# PSU-triple-voltage-eagle-6-branded.net
KiCad netlist of a schematic drawn in EAGLE
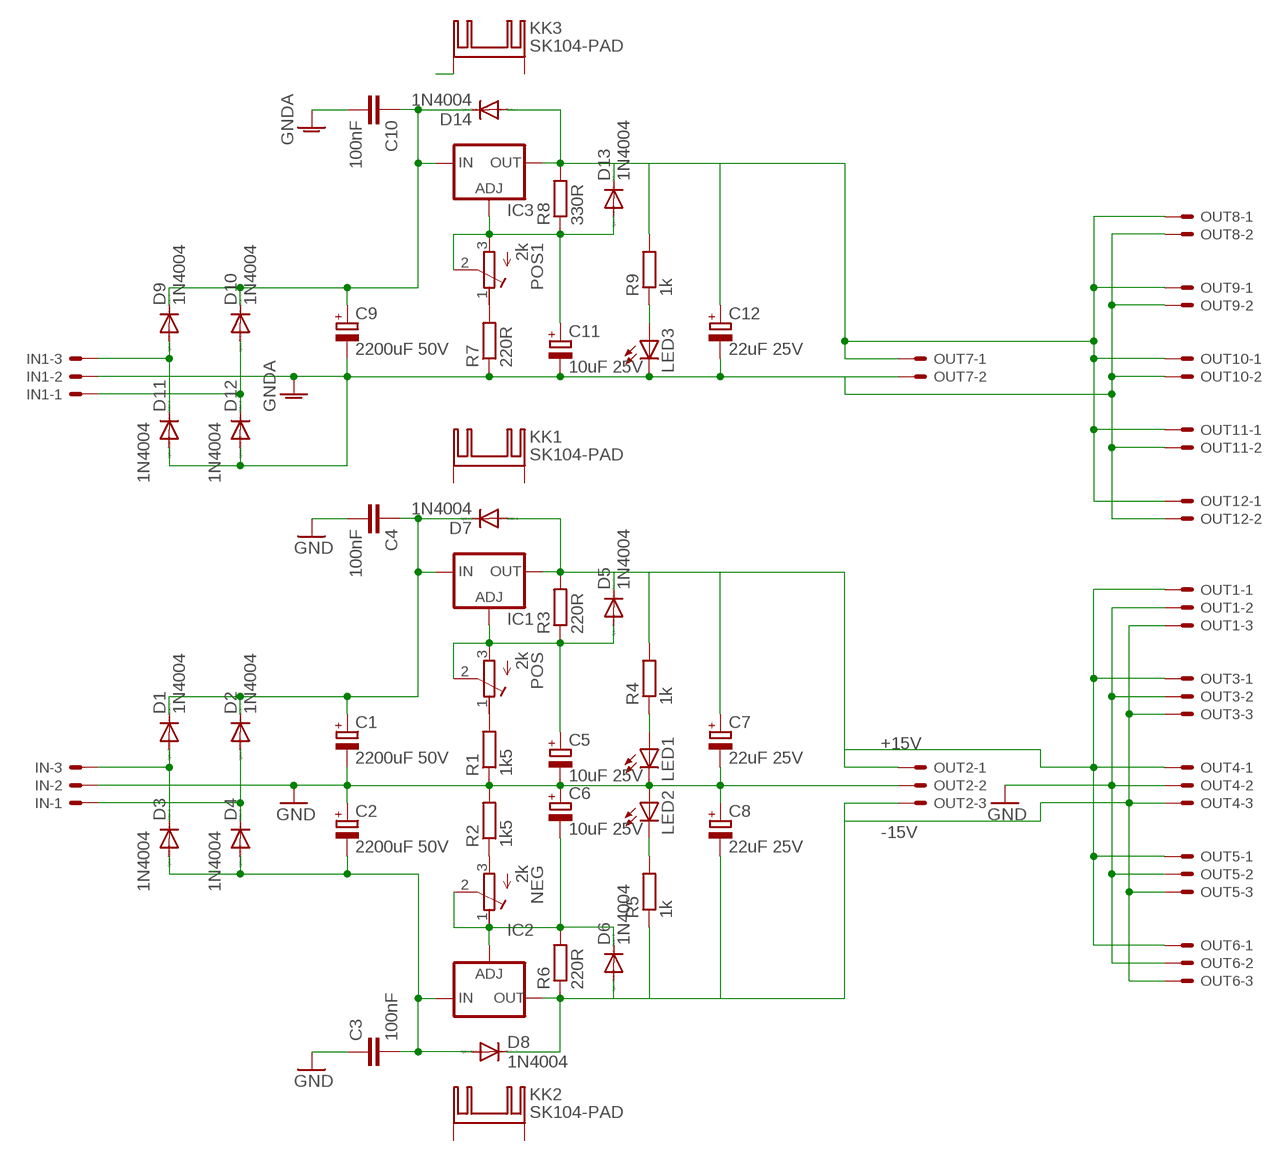
[diagram p0: schematic, sheet 1]

(export (version "E")
  (design (tool "Eeschema 10.0.6"))
  (components
    (comp (ref "C1")
      (value "2200uF 50V")
      (footprint "eagle-import:E7,5-16")
      (libsource (lib "eagle-import") (part "CPOL-EUE7.5-16"))
    )
    (comp (ref "C2")
      (value "2200uF 50V")
      (footprint "eagle-import:E7,5-16")
      (libsource (lib "eagle-import") (part "CPOL-EUE7.5-16"))
    )
    (comp (ref "C3")
      (value "100nF")
      (footprint "eagle-import:C050-025X075")
      (libsource (lib "eagle-import") (part "C-EU050-025X075"))
    )
    (comp (ref "C4")
      (value "100nF")
      (footprint "eagle-import:C050-025X075")
      (libsource (lib "eagle-import") (part "C-EU050-025X075"))
    )
    (comp (ref "C5")
      (value "10uF 25V")
      (footprint "eagle-import:E2,5-5")
      (libsource (lib "eagle-import") (part "CPOL-EUE2.5-5"))
    )
    (comp (ref "C6")
      (value "10uF 25V")
      (footprint "eagle-import:E2,5-5")
      (libsource (lib "eagle-import") (part "CPOL-EUE2.5-5"))
    )
    (comp (ref "C7")
      (value "22uF 25V")
      (footprint "eagle-import:E2,5-5")
      (libsource (lib "eagle-import") (part "CPOL-EUE2.5-5"))
    )
    (comp (ref "C8")
      (value "22uF 25V")
      (footprint "eagle-import:E2,5-5")
      (libsource (lib "eagle-import") (part "CPOL-EUE2.5-5"))
    )
    (comp (ref "C9")
      (value "2200uF 50V")
      (footprint "eagle-import:E7,5-16")
      (libsource (lib "eagle-import") (part "CPOL-EUE7.5-16"))
    )
    (comp (ref "C10")
      (value "100nF")
      (footprint "eagle-import:C050-025X075")
      (libsource (lib "eagle-import") (part "C-EU050-025X075"))
    )
    (comp (ref "C11")
      (value "10uF 25V")
      (footprint "eagle-import:E2,5-5")
      (libsource (lib "eagle-import") (part "CPOL-EUE2.5-5"))
    )
    (comp (ref "C12")
      (value "22uF 25V")
      (footprint "eagle-import:E2,5-5")
      (libsource (lib "eagle-import") (part "CPOL-EUE2.5-5"))
    )
    (comp (ref "D1")
      (value "1N4004")
      (footprint "eagle-import:DO41-10")
      (libsource (lib "eagle-import") (part "1N4004"))
    )
    (comp (ref "D2")
      (value "1N4004")
      (footprint "eagle-import:DO41-10")
      (libsource (lib "eagle-import") (part "1N4004"))
    )
    (comp (ref "D3")
      (value "1N4004")
      (footprint "eagle-import:DO41-10")
      (libsource (lib "eagle-import") (part "1N4004"))
    )
    (comp (ref "D4")
      (value "1N4004")
      (footprint "eagle-import:DO41-10")
      (libsource (lib "eagle-import") (part "1N4004"))
    )
    (comp (ref "D5")
      (value "1N4004")
      (footprint "eagle-import:DO41-10")
      (libsource (lib "eagle-import") (part "1N4004"))
    )
    (comp (ref "D6")
      (value "1N4004")
      (footprint "eagle-import:DO41-10")
      (libsource (lib "eagle-import") (part "1N4004"))
    )
    (comp (ref "D7")
      (value "1N4004")
      (footprint "eagle-import:DO41-10")
      (libsource (lib "eagle-import") (part "1N4004"))
    )
    (comp (ref "D8")
      (value "1N4004")
      (footprint "eagle-import:DO41-10")
      (libsource (lib "eagle-import") (part "1N4004"))
    )
    (comp (ref "D9")
      (value "1N4004")
      (footprint "eagle-import:DO41-10")
      (libsource (lib "eagle-import") (part "1N4004"))
    )
    (comp (ref "D10")
      (value "1N4004")
      (footprint "eagle-import:DO41-10")
      (libsource (lib "eagle-import") (part "1N4004"))
    )
    (comp (ref "D11")
      (value "1N4004")
      (footprint "eagle-import:DO41-10")
      (libsource (lib "eagle-import") (part "1N4004"))
    )
    (comp (ref "D12")
      (value "1N4004")
      (footprint "eagle-import:DO41-10")
      (libsource (lib "eagle-import") (part "1N4004"))
    )
    (comp (ref "D13")
      (value "1N4004")
      (footprint "eagle-import:DO41-10")
      (libsource (lib "eagle-import") (part "1N4004"))
    )
    (comp (ref "D14")
      (value "1N4004")
      (footprint "eagle-import:DO41-10")
      (libsource (lib "eagle-import") (part "1N4004"))
    )
    (comp (ref "IC1")
      (value "LM317TS")
      (footprint "eagle-import:317TS")
      (libsource (lib "eagle-import") (part "LM317TS"))
    )
    (comp (ref "IC2")
      (value "LM337TS")
      (footprint "eagle-import:337TS")
      (libsource (lib "eagle-import") (part "LM337TS"))
    )
    (comp (ref "IC3")
      (value "LM317TS")
      (footprint "eagle-import:317TS")
      (libsource (lib "eagle-import") (part "LM317TS"))
    )
    (comp (ref "IN")
      (value "KK-156-3")
      (footprint "eagle-import:KK-156-3")
      (libsource (lib "eagle-import") (part "KK-156-3"))
    )
    (comp (ref "IN1")
      (value "KK-156-3")
      (footprint "eagle-import:KK-156-3")
      (libsource (lib "eagle-import") (part "KK-156-3"))
    )
    (comp (ref "KK1")
      (value "SK104-PAD")
      (footprint "eagle-import:SK104-PAD")
      (libsource (lib "eagle-import") (part "SK104-PAD"))
    )
    (comp (ref "KK2")
      (value "SK104-PAD")
      (footprint "eagle-import:SK104-PAD")
      (libsource (lib "eagle-import") (part "SK104-PAD"))
    )
    (comp (ref "KK3")
      (value "SK104-PAD")
      (footprint "eagle-import:SK104-PAD")
      (libsource (lib "eagle-import") (part "SK104-PAD"))
    )
    (comp (ref "LED1")
      (value "LED3MM")
      (footprint "eagle-import:LED3MM")
      (libsource (lib "eagle-import") (part "LED3MM"))
    )
    (comp (ref "LED2")
      (value "LED3MM")
      (footprint "eagle-import:LED3MM")
      (libsource (lib "eagle-import") (part "LED3MM"))
    )
    (comp (ref "LED3")
      (value "LED3MM")
      (footprint "eagle-import:LED3MM")
      (libsource (lib "eagle-import") (part "LED3MM"))
    )
    (comp (ref "NEG")
      (value "2k")
      (footprint "eagle-import:RTRIMT93YA")
      (libsource (lib "eagle-import") (part "R-TRIMMT93YA"))
    )
    (comp (ref "OUT1")
      (value "KK-156-3")
      (footprint "eagle-import:KK-156-3")
      (libsource (lib "eagle-import") (part "KK-156-3"))
    )
    (comp (ref "OUT2")
      (value "KK-156-3")
      (footprint "eagle-import:KK-156-3")
      (libsource (lib "eagle-import") (part "KK-156-3"))
    )
    (comp (ref "OUT3")
      (value "KK-156-3")
      (footprint "eagle-import:KK-156-3")
      (libsource (lib "eagle-import") (part "KK-156-3"))
    )
    (comp (ref "OUT4")
      (value "KK-156-3")
      (footprint "eagle-import:KK-156-3")
      (libsource (lib "eagle-import") (part "KK-156-3"))
    )
    (comp (ref "OUT5")
      (value "KK-156-3")
      (footprint "eagle-import:KK-156-3")
      (libsource (lib "eagle-import") (part "KK-156-3"))
    )
    (comp (ref "OUT6")
      (value "KK-156-3")
      (footprint "eagle-import:KK-156-3")
      (libsource (lib "eagle-import") (part "KK-156-3"))
    )
    (comp (ref "OUT7")
      (value "KK-156-2")
      (footprint "eagle-import:KK-156-2")
      (libsource (lib "eagle-import") (part "KK-156-2"))
    )
    (comp (ref "OUT8")
      (value "KK-156-2")
      (footprint "eagle-import:KK-156-2")
      (libsource (lib "eagle-import") (part "KK-156-2"))
    )
    (comp (ref "OUT9")
      (value "KK-156-2")
      (footprint "eagle-import:KK-156-2")
      (libsource (lib "eagle-import") (part "KK-156-2"))
    )
    (comp (ref "OUT10")
      (value "KK-156-2")
      (footprint "eagle-import:KK-156-2")
      (libsource (lib "eagle-import") (part "KK-156-2"))
    )
    (comp (ref "OUT11")
      (value "KK-156-2")
      (footprint "eagle-import:KK-156-2")
      (libsource (lib "eagle-import") (part "KK-156-2"))
    )
    (comp (ref "OUT12")
      (value "KK-156-2")
      (footprint "eagle-import:KK-156-2")
      (libsource (lib "eagle-import") (part "KK-156-2"))
    )
    (comp (ref "POS")
      (value "2k")
      (footprint "eagle-import:RTRIMT93YA")
      (libsource (lib "eagle-import") (part "R-TRIMMT93YA"))
    )
    (comp (ref "POS1")
      (value "2k")
      (footprint "eagle-import:RTRIMT93YA")
      (libsource (lib "eagle-import") (part "R-TRIMMT93YA"))
    )
    (comp (ref "R1")
      (value "1k5")
      (footprint "eagle-import:0207_7")
      (libsource (lib "eagle-import") (part "R-EU_0207/7"))
    )
    (comp (ref "R2")
      (value "1k5")
      (footprint "eagle-import:0207_7")
      (libsource (lib "eagle-import") (part "R-EU_0207/7"))
    )
    (comp (ref "R3")
      (value "220R")
      (footprint "eagle-import:0207_7")
      (libsource (lib "eagle-import") (part "R-EU_0207/7"))
    )
    (comp (ref "R4")
      (value "1k")
      (footprint "eagle-import:0207_7")
      (libsource (lib "eagle-import") (part "R-EU_0207/7"))
    )
    (comp (ref "R5")
      (value "1k")
      (footprint "eagle-import:0207_7")
      (libsource (lib "eagle-import") (part "R-EU_0207/7"))
    )
    (comp (ref "R6")
      (value "220R")
      (footprint "eagle-import:0207_7")
      (libsource (lib "eagle-import") (part "R-EU_0207/7"))
    )
    (comp (ref "R7")
      (value "220R")
      (footprint "eagle-import:0207_7")
      (libsource (lib "eagle-import") (part "R-EU_0207/7"))
    )
    (comp (ref "R8")
      (value "330R")
      (footprint "eagle-import:0207_7")
      (libsource (lib "eagle-import") (part "R-EU_0207/7"))
    )
    (comp (ref "R9")
      (value "1k")
      (footprint "eagle-import:0207_7")
      (libsource (lib "eagle-import") (part "R-EU_0207/7"))
    )
  )
  (nets
    (net (code "1") (name "/+15V") (class "Default")
      (node (ref "C7") (pin "+") (pinfunction "+_+") (pintype "passive"))
      (node (ref "D5") (pin "C") (pinfunction "C_C") (pintype "passive"))
      (node (ref "D7") (pin "A") (pinfunction "A_A") (pintype "passive"))
      (node (ref "IC1") (pin "2") (pinfunction "OUT_2") (pintype "passive"))
      (node (ref "OUT1") (pin "1") (pinfunction "S_1") (pintype "passive"))
      (node (ref "OUT2") (pin "1") (pinfunction "S_1") (pintype "passive"))
      (node (ref "OUT3") (pin "1") (pinfunction "S_1") (pintype "passive"))
      (node (ref "OUT4") (pin "1") (pinfunction "S_1") (pintype "passive"))
      (node (ref "OUT5") (pin "1") (pinfunction "S_1") (pintype "passive"))
      (node (ref "OUT6") (pin "1") (pinfunction "S_1") (pintype "passive"))
      (node (ref "R3") (pin "2") (pinfunction "2_2") (pintype "passive"))
      (node (ref "R4") (pin "2") (pinfunction "2_2") (pintype "passive"))
    )
    (net (code "2") (name "/-15V") (class "Default")
      (node (ref "C8") (pin "-") (pinfunction "-_-") (pintype "passive"))
      (node (ref "D6") (pin "A") (pinfunction "A_A") (pintype "passive"))
      (node (ref "D8") (pin "C") (pinfunction "C_C") (pintype "passive"))
      (node (ref "IC2") (pin "3") (pinfunction "OUT_3") (pintype "passive"))
      (node (ref "OUT1") (pin "3") (pinfunction "S_3") (pintype "passive"))
      (node (ref "OUT2") (pin "3") (pinfunction "S_3") (pintype "passive"))
      (node (ref "OUT3") (pin "3") (pinfunction "S_3") (pintype "passive"))
      (node (ref "OUT4") (pin "3") (pinfunction "S_3") (pintype "passive"))
      (node (ref "OUT5") (pin "3") (pinfunction "S_3") (pintype "passive"))
      (node (ref "OUT6") (pin "3") (pinfunction "S_3") (pintype "passive"))
      (node (ref "R5") (pin "1") (pinfunction "1_1") (pintype "passive"))
      (node (ref "R6") (pin "1") (pinfunction "1_1") (pintype "passive"))
    )
    (net (code "3") (name "GND") (class "Default")
      (node (ref "C1") (pin "-") (pinfunction "-_-") (pintype "passive"))
      (node (ref "C2") (pin "+") (pinfunction "+_+") (pintype "passive"))
      (node (ref "C3") (pin "1") (pinfunction "1_1") (pintype "passive"))
      (node (ref "C4") (pin "2") (pinfunction "2_2") (pintype "passive"))
      (node (ref "C5") (pin "-") (pinfunction "-_-") (pintype "passive"))
      (node (ref "C6") (pin "+") (pinfunction "+_+") (pintype "passive"))
      (node (ref "C7") (pin "-") (pinfunction "-_-") (pintype "passive"))
      (node (ref "C8") (pin "+") (pinfunction "+_+") (pintype "passive"))
      (node (ref "IN") (pin "2") (pinfunction "S_2") (pintype "passive"))
      (node (ref "LED1") (pin "K") (pinfunction "C_K") (pintype "passive"))
      (node (ref "LED2") (pin "A") (pinfunction "A_A") (pintype "passive"))
      (node (ref "OUT1") (pin "2") (pinfunction "S_2") (pintype "passive"))
      (node (ref "OUT2") (pin "2") (pinfunction "S_2") (pintype "passive"))
      (node (ref "OUT3") (pin "2") (pinfunction "S_2") (pintype "passive"))
      (node (ref "OUT4") (pin "2") (pinfunction "S_2") (pintype "passive"))
      (node (ref "OUT5") (pin "2") (pinfunction "S_2") (pintype "passive"))
      (node (ref "OUT6") (pin "2") (pinfunction "S_2") (pintype "passive"))
      (node (ref "R1") (pin "1") (pinfunction "1_1") (pintype "passive"))
      (node (ref "R2") (pin "2") (pinfunction "2_2") (pintype "passive"))
    )
    (net (code "4") (name "GNDA") (class "Default")
      (node (ref "C10") (pin "2") (pinfunction "2_2") (pintype "passive"))
      (node (ref "C11") (pin "-") (pinfunction "-_-") (pintype "passive"))
      (node (ref "C12") (pin "-") (pinfunction "-_-") (pintype "passive"))
      (node (ref "C9") (pin "-") (pinfunction "-_-") (pintype "passive"))
      (node (ref "D11") (pin "A") (pinfunction "A_A") (pintype "passive"))
      (node (ref "D12") (pin "A") (pinfunction "A_A") (pintype "passive"))
      (node (ref "IN1") (pin "2") (pinfunction "S_2") (pintype "passive"))
      (node (ref "LED3") (pin "K") (pinfunction "C_K") (pintype "passive"))
      (node (ref "OUT10") (pin "2") (pinfunction "S_2") (pintype "passive"))
      (node (ref "OUT11") (pin "2") (pinfunction "S_2") (pintype "passive"))
      (node (ref "OUT12") (pin "2") (pinfunction "S_2") (pintype "passive"))
      (node (ref "OUT7") (pin "2") (pinfunction "S_2") (pintype "passive"))
      (node (ref "OUT8") (pin "2") (pinfunction "S_2") (pintype "passive"))
      (node (ref "OUT9") (pin "2") (pinfunction "S_2") (pintype "passive"))
      (node (ref "R7") (pin "1") (pinfunction "1_1") (pintype "passive"))
    )
    (net (code "5") (name "Net-(IC1-ADJ)") (class "Default")
      (node (ref "C5") (pin "+") (pinfunction "+_+") (pintype "passive"))
      (node (ref "D5") (pin "A") (pinfunction "A_A") (pintype "passive"))
      (node (ref "IC1") (pin "1") (pinfunction "ADJ_1") (pintype "input"))
      (node (ref "POS") (pin "2") (pinfunction "S_2") (pintype "passive"))
      (node (ref "POS") (pin "3") (pinfunction "A_3") (pintype "passive"))
      (node (ref "R3") (pin "1") (pinfunction "1_1") (pintype "passive"))
    )
    (net (code "6") (name "Net-(IC1-IN)") (class "Default")
      (node (ref "C1") (pin "+") (pinfunction "+_+") (pintype "passive"))
      (node (ref "C4") (pin "1") (pinfunction "1_1") (pintype "passive"))
      (node (ref "D1") (pin "C") (pinfunction "C_C") (pintype "passive"))
      (node (ref "D2") (pin "C") (pinfunction "C_C") (pintype "passive"))
      (node (ref "D7") (pin "C") (pinfunction "C_C") (pintype "passive"))
      (node (ref "IC1") (pin "3") (pinfunction "IN_3") (pintype "input"))
    )
    (net (code "7") (name "Net-(IC2-ADJ)") (class "Default")
      (node (ref "C6") (pin "-") (pinfunction "-_-") (pintype "passive"))
      (node (ref "D6") (pin "C") (pinfunction "C_C") (pintype "passive"))
      (node (ref "IC2") (pin "1") (pinfunction "ADJ_1") (pintype "input"))
      (node (ref "NEG") (pin "1") (pinfunction "E_1") (pintype "passive"))
      (node (ref "NEG") (pin "2") (pinfunction "S_2") (pintype "passive"))
      (node (ref "R6") (pin "2") (pinfunction "2_2") (pintype "passive"))
    )
    (net (code "8") (name "Net-(IC2-IN)") (class "Default")
      (node (ref "C2") (pin "-") (pinfunction "-_-") (pintype "passive"))
      (node (ref "C3") (pin "2") (pinfunction "2_2") (pintype "passive"))
      (node (ref "D3") (pin "A") (pinfunction "A_A") (pintype "passive"))
      (node (ref "D4") (pin "A") (pinfunction "A_A") (pintype "passive"))
      (node (ref "D8") (pin "A") (pinfunction "A_A") (pintype "passive"))
      (node (ref "IC2") (pin "2") (pinfunction "IN_2") (pintype "input"))
    )
    (net (code "9") (name "Net-(IC3-ADJ)") (class "Default")
      (node (ref "C11") (pin "+") (pinfunction "+_+") (pintype "passive"))
      (node (ref "D13") (pin "A") (pinfunction "A_A") (pintype "passive"))
      (node (ref "IC3") (pin "1") (pinfunction "ADJ_1") (pintype "input"))
      (node (ref "POS1") (pin "2") (pinfunction "S_2") (pintype "passive"))
      (node (ref "POS1") (pin "3") (pinfunction "A_3") (pintype "passive"))
      (node (ref "R8") (pin "1") (pinfunction "1_1") (pintype "passive"))
    )
    (net (code "10") (name "Net-(IC3-IN)") (class "Default")
      (node (ref "C10") (pin "1") (pinfunction "1_1") (pintype "passive"))
      (node (ref "C9") (pin "+") (pinfunction "+_+") (pintype "passive"))
      (node (ref "D10") (pin "C") (pinfunction "C_C") (pintype "passive"))
      (node (ref "D14") (pin "C") (pinfunction "C_C") (pintype "passive"))
      (node (ref "D9") (pin "C") (pinfunction "C_C") (pintype "passive"))
      (node (ref "IC3") (pin "3") (pinfunction "IN_3") (pintype "input"))
    )
    (net (code "11") (name "Net-(IC3-OUT)") (class "Default")
      (node (ref "C12") (pin "+") (pinfunction "+_+") (pintype "passive"))
      (node (ref "D13") (pin "C") (pinfunction "C_C") (pintype "passive"))
      (node (ref "D14") (pin "A") (pinfunction "A_A") (pintype "passive"))
      (node (ref "IC3") (pin "2") (pinfunction "OUT_2") (pintype "passive"))
      (node (ref "OUT10") (pin "1") (pinfunction "S_1") (pintype "passive"))
      (node (ref "OUT11") (pin "1") (pinfunction "S_1") (pintype "passive"))
      (node (ref "OUT12") (pin "1") (pinfunction "S_1") (pintype "passive"))
      (node (ref "OUT7") (pin "1") (pinfunction "S_1") (pintype "passive"))
      (node (ref "OUT8") (pin "1") (pinfunction "S_1") (pintype "passive"))
      (node (ref "OUT9") (pin "1") (pinfunction "S_1") (pintype "passive"))
      (node (ref "R8") (pin "2") (pinfunction "2_2") (pintype "passive"))
      (node (ref "R9") (pin "2") (pinfunction "2_2") (pintype "passive"))
    )
    (net (code "12") (name "Net-(IN1A-S)") (class "Default")
      (node (ref "D10") (pin "A") (pinfunction "A_A") (pintype "passive"))
      (node (ref "D12") (pin "C") (pinfunction "C_C") (pintype "passive"))
      (node (ref "IN1") (pin "1") (pinfunction "S_1") (pintype "passive"))
    )
    (net (code "13") (name "Net-(IN1C-S)") (class "Default")
      (node (ref "D11") (pin "C") (pinfunction "C_C") (pintype "passive"))
      (node (ref "D9") (pin "A") (pinfunction "A_A") (pintype "passive"))
      (node (ref "IN1") (pin "3") (pinfunction "S_3") (pintype "passive"))
    )
    (net (code "14") (name "Net-(INA-S)") (class "Default")
      (node (ref "D2") (pin "A") (pinfunction "A_A") (pintype "passive"))
      (node (ref "D4") (pin "C") (pinfunction "C_C") (pintype "passive"))
      (node (ref "IN") (pin "1") (pinfunction "S_1") (pintype "passive"))
    )
    (net (code "15") (name "Net-(INC-S)") (class "Default")
      (node (ref "D1") (pin "A") (pinfunction "A_A") (pintype "passive"))
      (node (ref "D3") (pin "C") (pinfunction "C_C") (pintype "passive"))
      (node (ref "IN") (pin "3") (pinfunction "S_3") (pintype "passive"))
    )
    (net (code "16") (name "Net-(LED1-PadA)") (class "Default")
      (node (ref "LED1") (pin "A") (pinfunction "A_A") (pintype "passive"))
      (node (ref "R4") (pin "1") (pinfunction "1_1") (pintype "passive"))
    )
    (net (code "17") (name "Net-(LED2-C)") (class "Default")
      (node (ref "LED2") (pin "K") (pinfunction "C_K") (pintype "passive"))
      (node (ref "R5") (pin "2") (pinfunction "2_2") (pintype "passive"))
    )
    (net (code "18") (name "Net-(LED3-PadA)") (class "Default")
      (node (ref "LED3") (pin "A") (pinfunction "A_A") (pintype "passive"))
      (node (ref "R9") (pin "1") (pinfunction "1_1") (pintype "passive"))
    )
    (net (code "19") (name "Net-(NEG-A)") (class "Default")
      (node (ref "NEG") (pin "3") (pinfunction "A_3") (pintype "passive"))
      (node (ref "R2") (pin "1") (pinfunction "1_1") (pintype "passive"))
    )
    (net (code "20") (name "Net-(POS-E)") (class "Default")
      (node (ref "POS") (pin "1") (pinfunction "E_1") (pintype "passive"))
      (node (ref "R1") (pin "2") (pinfunction "2_2") (pintype "passive"))
    )
    (net (code "21") (name "Net-(POS1-E)") (class "Default")
      (node (ref "POS1") (pin "1") (pinfunction "E_1") (pintype "passive"))
      (node (ref "R7") (pin "2") (pinfunction "2_2") (pintype "passive"))
    )
    (net (code "22") (name "unconnected-(KK1-K-PadK1)") (class "Default")
      (node (ref "KK1") (pin "K1") (pinfunction "K_K1") (pintype "passive"))
    )
    (net (code "23") (name "unconnected-(KK1-K-PadK2)") (class "Default")
      (node (ref "KK1") (pin "K2") (pinfunction "K_K2") (pintype "passive"))
    )
    (net (code "24") (name "unconnected-(KK2-K-PadK1)") (class "Default")
      (node (ref "KK2") (pin "K1") (pinfunction "K_K1") (pintype "passive"))
    )
    (net (code "25") (name "unconnected-(KK2-K-PadK2)") (class "Default")
      (node (ref "KK2") (pin "K2") (pinfunction "K_K2") (pintype "passive"))
    )
    (net (code "26") (name "unconnected-(KK3-K-PadK1)") (class "Default")
      (node (ref "KK3") (pin "K1") (pinfunction "K_K1") (pintype "passive"))
    )
    (net (code "27") (name "unconnected-(KK3-K-PadK2)") (class "Default")
      (node (ref "KK3") (pin "K2") (pinfunction "K_K2") (pintype "passive"))
    )
  )
)
